# Shift-Rgisters.net
KiCad netlist of a schematic drawn in EAGLE
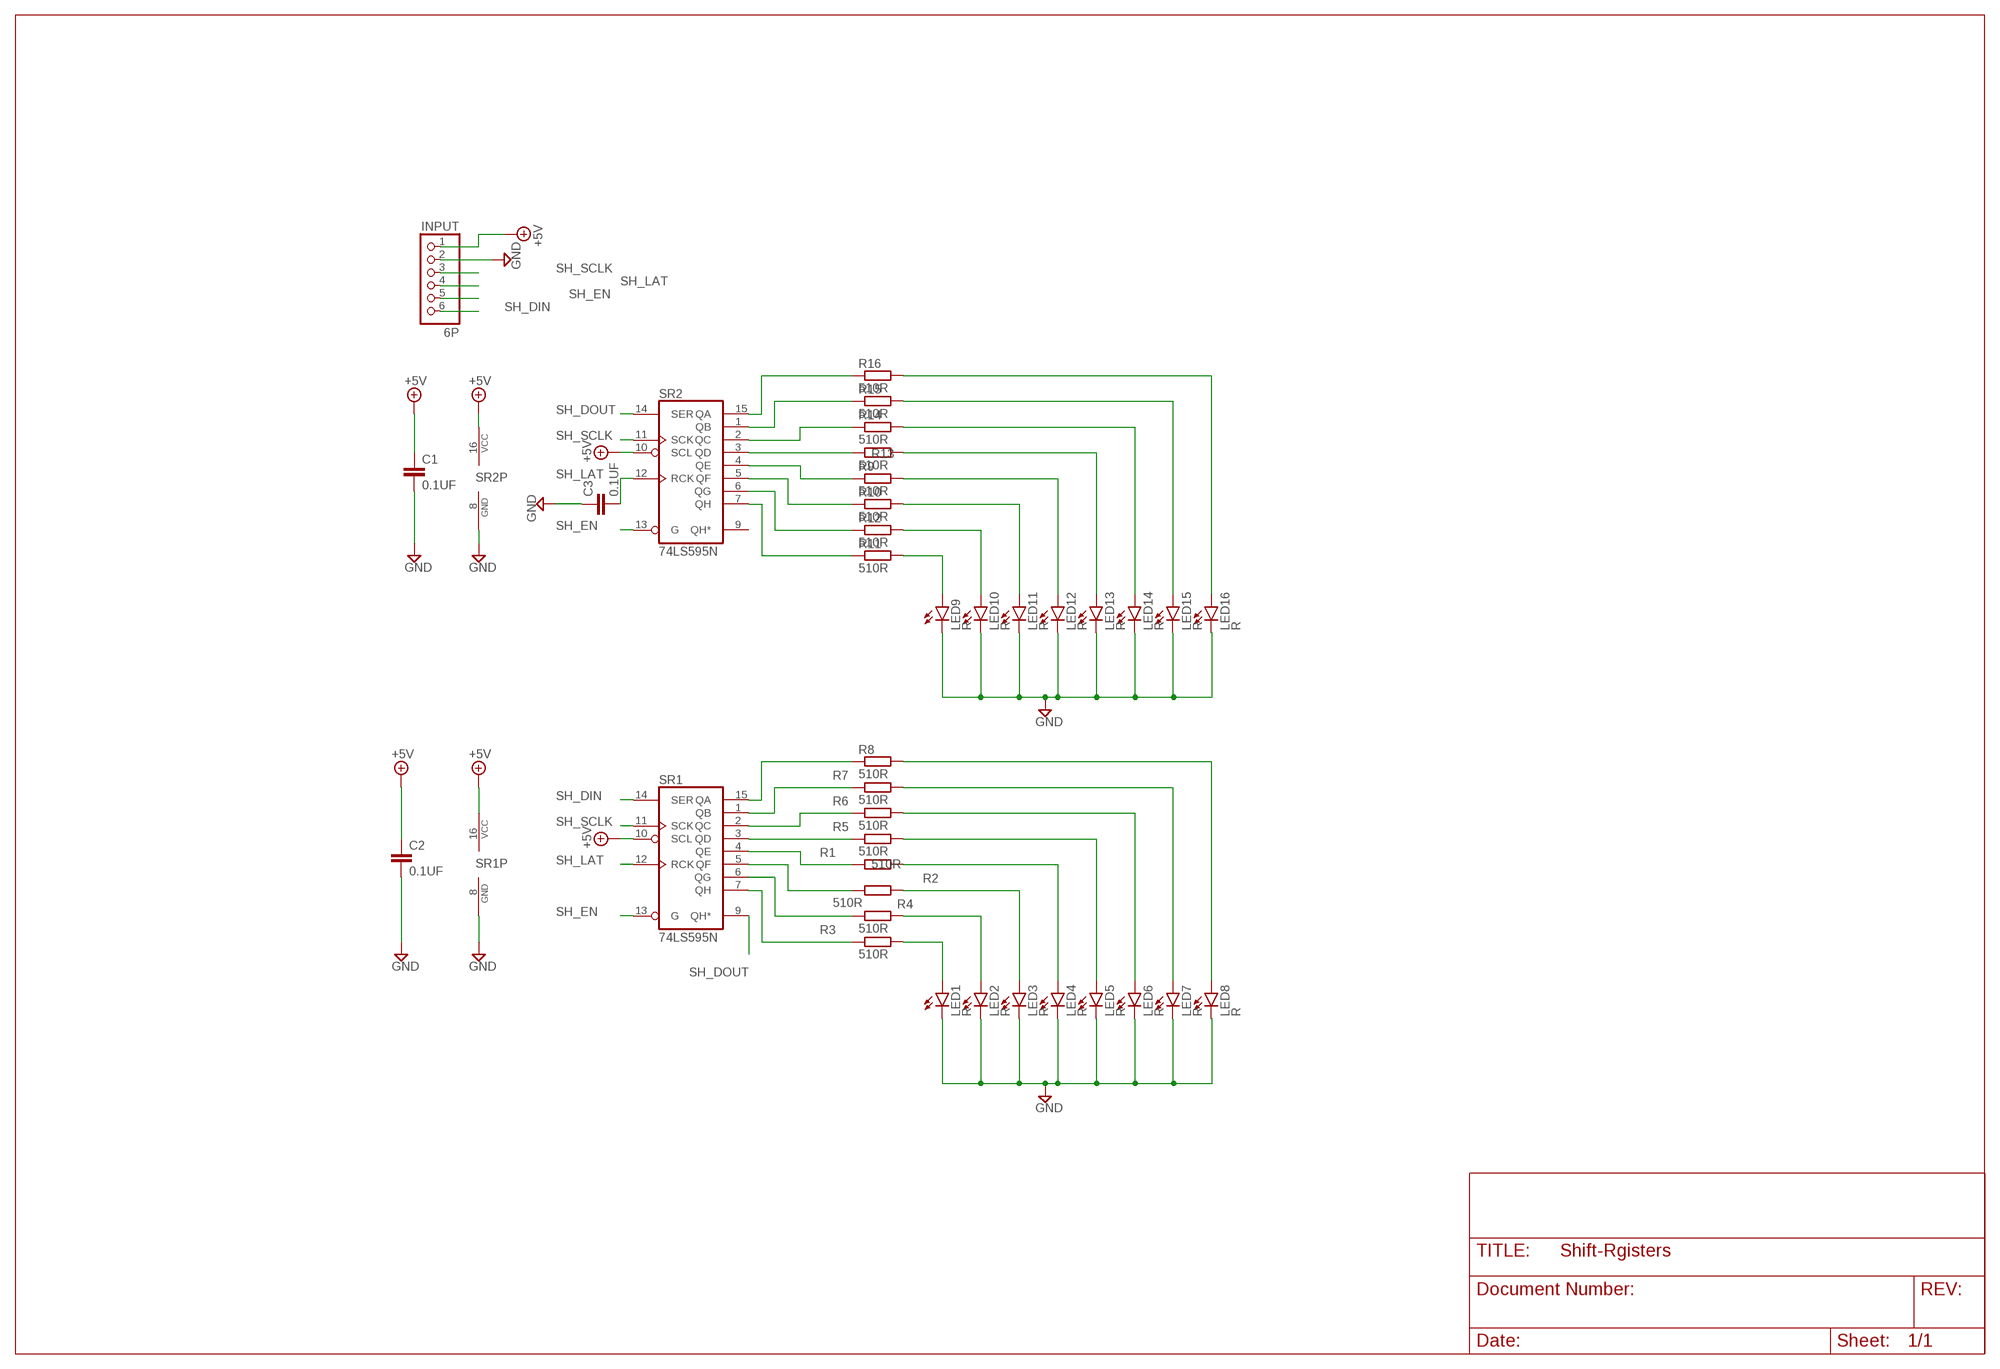
[diagram p0: schematic, sheet 1]

(export (version "E")
  (design (tool "Eeschema 10.0.6"))
  (components
    (comp (ref "C1")
      (value "0.1UF")
      (footprint "eagle-import:C050-030X075")
      (libsource (lib "eagle-import") (part "C-EU050-030X075"))
    )
    (comp (ref "C2")
      (value "0.1UF")
      (footprint "eagle-import:C050-030X075")
      (libsource (lib "eagle-import") (part "C-EU050-030X075"))
    )
    (comp (ref "C3")
      (value "0.1UF")
      (footprint "eagle-import:C050-030X075")
      (libsource (lib "eagle-import") (part "C-EU050-030X075"))
    )
    (comp (ref "INPUT")
      (value "6P")
      (footprint "eagle-import:1X06")
      (libsource (lib "eagle-import") (part "PINHD-1X6"))
    )
    (comp (ref "LED1")
      (value "R")
      (footprint "eagle-import:LED5MM")
      (libsource (lib "eagle-import") (part "LED5MM"))
    )
    (comp (ref "LED2")
      (value "R")
      (footprint "eagle-import:LED5MM")
      (libsource (lib "eagle-import") (part "LED5MM"))
    )
    (comp (ref "LED3")
      (value "R")
      (footprint "eagle-import:LED5MM")
      (libsource (lib "eagle-import") (part "LED5MM"))
    )
    (comp (ref "LED4")
      (value "R")
      (footprint "eagle-import:LED5MM")
      (libsource (lib "eagle-import") (part "LED5MM"))
    )
    (comp (ref "LED5")
      (value "R")
      (footprint "eagle-import:LED5MM")
      (libsource (lib "eagle-import") (part "LED5MM"))
    )
    (comp (ref "LED6")
      (value "R")
      (footprint "eagle-import:LED5MM")
      (libsource (lib "eagle-import") (part "LED5MM"))
    )
    (comp (ref "LED7")
      (value "R")
      (footprint "eagle-import:LED5MM")
      (libsource (lib "eagle-import") (part "LED5MM"))
    )
    (comp (ref "LED8")
      (value "R")
      (footprint "eagle-import:LED5MM")
      (libsource (lib "eagle-import") (part "LED5MM"))
    )
    (comp (ref "LED9")
      (value "R")
      (footprint "eagle-import:LED5MM")
      (libsource (lib "eagle-import") (part "LED5MM"))
    )
    (comp (ref "LED10")
      (value "R")
      (footprint "eagle-import:LED5MM")
      (libsource (lib "eagle-import") (part "LED5MM"))
    )
    (comp (ref "LED11")
      (value "R")
      (footprint "eagle-import:LED5MM")
      (libsource (lib "eagle-import") (part "LED5MM"))
    )
    (comp (ref "LED12")
      (value "R")
      (footprint "eagle-import:LED5MM")
      (libsource (lib "eagle-import") (part "LED5MM"))
    )
    (comp (ref "LED13")
      (value "R")
      (footprint "eagle-import:LED5MM")
      (libsource (lib "eagle-import") (part "LED5MM"))
    )
    (comp (ref "LED14")
      (value "R")
      (footprint "eagle-import:LED5MM")
      (libsource (lib "eagle-import") (part "LED5MM"))
    )
    (comp (ref "LED15")
      (value "R")
      (footprint "eagle-import:LED5MM")
      (libsource (lib "eagle-import") (part "LED5MM"))
    )
    (comp (ref "LED16")
      (value "R")
      (footprint "eagle-import:LED5MM")
      (libsource (lib "eagle-import") (part "LED5MM"))
    )
    (comp (ref "R1")
      (value "510R")
      (footprint "eagle-import:0207_10")
      (libsource (lib "eagle-import") (part "R-EU_0207/10"))
    )
    (comp (ref "R2")
      (value "510R")
      (footprint "eagle-import:0207_10")
      (libsource (lib "eagle-import") (part "R-EU_0207/10"))
    )
    (comp (ref "R3")
      (value "510R")
      (footprint "eagle-import:0207_10")
      (libsource (lib "eagle-import") (part "R-EU_0207/10"))
    )
    (comp (ref "R4")
      (value "510R")
      (footprint "eagle-import:0207_10")
      (libsource (lib "eagle-import") (part "R-EU_0207/10"))
    )
    (comp (ref "R5")
      (value "510R")
      (footprint "eagle-import:0207_10")
      (libsource (lib "eagle-import") (part "R-EU_0207/10"))
    )
    (comp (ref "R6")
      (value "510R")
      (footprint "eagle-import:0207_10")
      (libsource (lib "eagle-import") (part "R-EU_0207/10"))
    )
    (comp (ref "R7")
      (value "510R")
      (footprint "eagle-import:0207_10")
      (libsource (lib "eagle-import") (part "R-EU_0207/10"))
    )
    (comp (ref "R8")
      (value "510R")
      (footprint "eagle-import:0207_10")
      (libsource (lib "eagle-import") (part "R-EU_0207/10"))
    )
    (comp (ref "R9")
      (value "510R")
      (footprint "eagle-import:0207_10")
      (libsource (lib "eagle-import") (part "R-EU_0207/10"))
    )
    (comp (ref "R10")
      (value "510R")
      (footprint "eagle-import:0207_10")
      (libsource (lib "eagle-import") (part "R-EU_0207/10"))
    )
    (comp (ref "R11")
      (value "510R")
      (footprint "eagle-import:0207_10")
      (libsource (lib "eagle-import") (part "R-EU_0207/10"))
    )
    (comp (ref "R12")
      (value "510R")
      (footprint "eagle-import:0207_10")
      (libsource (lib "eagle-import") (part "R-EU_0207/10"))
    )
    (comp (ref "R13")
      (value "510R")
      (footprint "eagle-import:0207_10")
      (libsource (lib "eagle-import") (part "R-EU_0207/10"))
    )
    (comp (ref "R14")
      (value "510R")
      (footprint "eagle-import:0207_10")
      (libsource (lib "eagle-import") (part "R-EU_0207/10"))
    )
    (comp (ref "R15")
      (value "510R")
      (footprint "eagle-import:0207_10")
      (libsource (lib "eagle-import") (part "R-EU_0207/10"))
    )
    (comp (ref "R16")
      (value "510R")
      (footprint "eagle-import:0207_10")
      (libsource (lib "eagle-import") (part "R-EU_0207/10"))
    )
    (comp (ref "SR1")
      (value "74LS595N")
      (footprint "eagle-import:DIL16")
      (libsource (lib "eagle-import") (part "74595NLS"))
    )
    (comp (ref "SR2")
      (value "74LS595N")
      (footprint "eagle-import:DIL16")
      (libsource (lib "eagle-import") (part "74595NLS"))
    )
  )
  (nets
    (net (code "1") (name "+5V") (class "Default")
      (node (ref "C1") (pin "1") (pinfunction "1_1") (pintype "passive"))
      (node (ref "C2") (pin "1") (pinfunction "1_1") (pintype "passive"))
      (node (ref "INPUT") (pin "1") (pinfunction "1_1") (pintype "passive"))
      (node (ref "SR1") (pin "10") (pinfunction "SCL_10") (pintype "input"))
      (node (ref "SR1") (pin "16") (pinfunction "VCC_16") (pintype "power_in"))
      (node (ref "SR2") (pin "10") (pinfunction "SCL_10") (pintype "input"))
      (node (ref "SR2") (pin "16") (pinfunction "VCC_16") (pintype "power_in"))
    )
    (net (code "2") (name "/SH_DIN") (class "Default")
      (node (ref "INPUT") (pin "6") (pinfunction "6_6") (pintype "passive"))
      (node (ref "SR1") (pin "14") (pinfunction "SER_14") (pintype "input"))
    )
    (net (code "3") (name "/SH_DOUT") (class "Default")
      (node (ref "SR1") (pin "9") (pinfunction "QH*_9") (pintype "tri_state"))
      (node (ref "SR2") (pin "14") (pinfunction "SER_14") (pintype "input"))
    )
    (net (code "4") (name "/SH_EN") (class "Default")
      (node (ref "INPUT") (pin "5") (pinfunction "5_5") (pintype "passive"))
      (node (ref "SR1") (pin "13") (pinfunction "G_13") (pintype "input"))
      (node (ref "SR2") (pin "13") (pinfunction "G_13") (pintype "input"))
    )
    (net (code "5") (name "/SH_LAT") (class "Default")
      (node (ref "C3") (pin "2") (pinfunction "2_2") (pintype "passive"))
      (node (ref "INPUT") (pin "4") (pinfunction "4_4") (pintype "passive"))
      (node (ref "SR1") (pin "12") (pinfunction "RCK_12") (pintype "input"))
      (node (ref "SR2") (pin "12") (pinfunction "RCK_12") (pintype "input"))
    )
    (net (code "6") (name "/SH_SCLK") (class "Default")
      (node (ref "INPUT") (pin "3") (pinfunction "3_3") (pintype "passive"))
      (node (ref "SR1") (pin "11") (pinfunction "SCK_11") (pintype "input"))
      (node (ref "SR2") (pin "11") (pinfunction "SCK_11") (pintype "input"))
    )
    (net (code "7") (name "GND") (class "Default")
      (node (ref "C1") (pin "2") (pinfunction "2_2") (pintype "passive"))
      (node (ref "C2") (pin "2") (pinfunction "2_2") (pintype "passive"))
      (node (ref "C3") (pin "1") (pinfunction "1_1") (pintype "passive"))
      (node (ref "INPUT") (pin "2") (pinfunction "2_2") (pintype "passive"))
      (node (ref "LED1") (pin "K") (pinfunction "C_K") (pintype "passive"))
      (node (ref "LED10") (pin "K") (pinfunction "C_K") (pintype "passive"))
      (node (ref "LED11") (pin "K") (pinfunction "C_K") (pintype "passive"))
      (node (ref "LED12") (pin "K") (pinfunction "C_K") (pintype "passive"))
      (node (ref "LED13") (pin "K") (pinfunction "C_K") (pintype "passive"))
      (node (ref "LED14") (pin "K") (pinfunction "C_K") (pintype "passive"))
      (node (ref "LED15") (pin "K") (pinfunction "C_K") (pintype "passive"))
      (node (ref "LED16") (pin "K") (pinfunction "C_K") (pintype "passive"))
      (node (ref "LED2") (pin "K") (pinfunction "C_K") (pintype "passive"))
      (node (ref "LED3") (pin "K") (pinfunction "C_K") (pintype "passive"))
      (node (ref "LED4") (pin "K") (pinfunction "C_K") (pintype "passive"))
      (node (ref "LED5") (pin "K") (pinfunction "C_K") (pintype "passive"))
      (node (ref "LED6") (pin "K") (pinfunction "C_K") (pintype "passive"))
      (node (ref "LED7") (pin "K") (pinfunction "C_K") (pintype "passive"))
      (node (ref "LED8") (pin "K") (pinfunction "C_K") (pintype "passive"))
      (node (ref "LED9") (pin "K") (pinfunction "C_K") (pintype "passive"))
      (node (ref "SR1") (pin "8") (pinfunction "GND_8") (pintype "power_in"))
      (node (ref "SR2") (pin "8") (pinfunction "GND_8") (pintype "power_in"))
    )
    (net (code "8") (name "Net-(LED1-PadA)") (class "Default")
      (node (ref "LED1") (pin "A") (pinfunction "A_A") (pintype "passive"))
      (node (ref "R3") (pin "2") (pinfunction "2_2") (pintype "passive"))
    )
    (net (code "9") (name "Net-(LED2-PadA)") (class "Default")
      (node (ref "LED2") (pin "A") (pinfunction "A_A") (pintype "passive"))
      (node (ref "R4") (pin "2") (pinfunction "2_2") (pintype "passive"))
    )
    (net (code "10") (name "Net-(LED3-PadA)") (class "Default")
      (node (ref "LED3") (pin "A") (pinfunction "A_A") (pintype "passive"))
      (node (ref "R2") (pin "2") (pinfunction "2_2") (pintype "passive"))
    )
    (net (code "11") (name "Net-(LED4-PadA)") (class "Default")
      (node (ref "LED4") (pin "A") (pinfunction "A_A") (pintype "passive"))
      (node (ref "R1") (pin "2") (pinfunction "2_2") (pintype "passive"))
    )
    (net (code "12") (name "Net-(LED5-PadA)") (class "Default")
      (node (ref "LED5") (pin "A") (pinfunction "A_A") (pintype "passive"))
      (node (ref "R5") (pin "2") (pinfunction "2_2") (pintype "passive"))
    )
    (net (code "13") (name "Net-(LED6-PadA)") (class "Default")
      (node (ref "LED6") (pin "A") (pinfunction "A_A") (pintype "passive"))
      (node (ref "R6") (pin "2") (pinfunction "2_2") (pintype "passive"))
    )
    (net (code "14") (name "Net-(LED7-PadA)") (class "Default")
      (node (ref "LED7") (pin "A") (pinfunction "A_A") (pintype "passive"))
      (node (ref "R7") (pin "2") (pinfunction "2_2") (pintype "passive"))
    )
    (net (code "15") (name "Net-(LED8-PadA)") (class "Default")
      (node (ref "LED8") (pin "A") (pinfunction "A_A") (pintype "passive"))
      (node (ref "R8") (pin "2") (pinfunction "2_2") (pintype "passive"))
    )
    (net (code "16") (name "Net-(LED9-PadA)") (class "Default")
      (node (ref "LED9") (pin "A") (pinfunction "A_A") (pintype "passive"))
      (node (ref "R11") (pin "2") (pinfunction "2_2") (pintype "passive"))
    )
    (net (code "17") (name "Net-(LED10-PadA)") (class "Default")
      (node (ref "LED10") (pin "A") (pinfunction "A_A") (pintype "passive"))
      (node (ref "R12") (pin "2") (pinfunction "2_2") (pintype "passive"))
    )
    (net (code "18") (name "Net-(LED11-PadA)") (class "Default")
      (node (ref "LED11") (pin "A") (pinfunction "A_A") (pintype "passive"))
      (node (ref "R10") (pin "2") (pinfunction "2_2") (pintype "passive"))
    )
    (net (code "19") (name "Net-(LED12-PadA)") (class "Default")
      (node (ref "LED12") (pin "A") (pinfunction "A_A") (pintype "passive"))
      (node (ref "R9") (pin "2") (pinfunction "2_2") (pintype "passive"))
    )
    (net (code "20") (name "Net-(LED13-PadA)") (class "Default")
      (node (ref "LED13") (pin "A") (pinfunction "A_A") (pintype "passive"))
      (node (ref "R13") (pin "2") (pinfunction "2_2") (pintype "passive"))
    )
    (net (code "21") (name "Net-(LED14-PadA)") (class "Default")
      (node (ref "LED14") (pin "A") (pinfunction "A_A") (pintype "passive"))
      (node (ref "R14") (pin "2") (pinfunction "2_2") (pintype "passive"))
    )
    (net (code "22") (name "Net-(LED15-PadA)") (class "Default")
      (node (ref "LED15") (pin "A") (pinfunction "A_A") (pintype "passive"))
      (node (ref "R15") (pin "2") (pinfunction "2_2") (pintype "passive"))
    )
    (net (code "23") (name "Net-(LED16-PadA)") (class "Default")
      (node (ref "LED16") (pin "A") (pinfunction "A_A") (pintype "passive"))
      (node (ref "R16") (pin "2") (pinfunction "2_2") (pintype "passive"))
    )
    (net (code "24") (name "Net-(SR1A-QA)") (class "Default")
      (node (ref "R8") (pin "1") (pinfunction "1_1") (pintype "passive"))
      (node (ref "SR1") (pin "15") (pinfunction "QA_15") (pintype "tri_state"))
    )
    (net (code "25") (name "Net-(SR1A-QB)") (class "Default")
      (node (ref "R7") (pin "1") (pinfunction "1_1") (pintype "passive"))
      (node (ref "SR1") (pin "1") (pinfunction "QB_1") (pintype "tri_state"))
    )
    (net (code "26") (name "Net-(SR1A-QC)") (class "Default")
      (node (ref "R6") (pin "1") (pinfunction "1_1") (pintype "passive"))
      (node (ref "SR1") (pin "2") (pinfunction "QC_2") (pintype "tri_state"))
    )
    (net (code "27") (name "Net-(SR1A-QD)") (class "Default")
      (node (ref "R5") (pin "1") (pinfunction "1_1") (pintype "passive"))
      (node (ref "SR1") (pin "3") (pinfunction "QD_3") (pintype "tri_state"))
    )
    (net (code "28") (name "Net-(SR1A-QE)") (class "Default")
      (node (ref "R1") (pin "1") (pinfunction "1_1") (pintype "passive"))
      (node (ref "SR1") (pin "4") (pinfunction "QE_4") (pintype "tri_state"))
    )
    (net (code "29") (name "Net-(SR1A-QF)") (class "Default")
      (node (ref "R2") (pin "1") (pinfunction "1_1") (pintype "passive"))
      (node (ref "SR1") (pin "5") (pinfunction "QF_5") (pintype "tri_state"))
    )
    (net (code "30") (name "Net-(SR1A-QG)") (class "Default")
      (node (ref "R4") (pin "1") (pinfunction "1_1") (pintype "passive"))
      (node (ref "SR1") (pin "6") (pinfunction "QG_6") (pintype "tri_state"))
    )
    (net (code "31") (name "Net-(SR1A-QH)") (class "Default")
      (node (ref "R3") (pin "1") (pinfunction "1_1") (pintype "passive"))
      (node (ref "SR1") (pin "7") (pinfunction "QH_7") (pintype "tri_state"))
    )
    (net (code "32") (name "Net-(SR2A-QA)") (class "Default")
      (node (ref "R16") (pin "1") (pinfunction "1_1") (pintype "passive"))
      (node (ref "SR2") (pin "15") (pinfunction "QA_15") (pintype "tri_state"))
    )
    (net (code "33") (name "Net-(SR2A-QB)") (class "Default")
      (node (ref "R15") (pin "1") (pinfunction "1_1") (pintype "passive"))
      (node (ref "SR2") (pin "1") (pinfunction "QB_1") (pintype "tri_state"))
    )
    (net (code "34") (name "Net-(SR2A-QC)") (class "Default")
      (node (ref "R14") (pin "1") (pinfunction "1_1") (pintype "passive"))
      (node (ref "SR2") (pin "2") (pinfunction "QC_2") (pintype "tri_state"))
    )
    (net (code "35") (name "Net-(SR2A-QD)") (class "Default")
      (node (ref "R13") (pin "1") (pinfunction "1_1") (pintype "passive"))
      (node (ref "SR2") (pin "3") (pinfunction "QD_3") (pintype "tri_state"))
    )
    (net (code "36") (name "Net-(SR2A-QE)") (class "Default")
      (node (ref "R9") (pin "1") (pinfunction "1_1") (pintype "passive"))
      (node (ref "SR2") (pin "4") (pinfunction "QE_4") (pintype "tri_state"))
    )
    (net (code "37") (name "Net-(SR2A-QF)") (class "Default")
      (node (ref "R10") (pin "1") (pinfunction "1_1") (pintype "passive"))
      (node (ref "SR2") (pin "5") (pinfunction "QF_5") (pintype "tri_state"))
    )
    (net (code "38") (name "Net-(SR2A-QG)") (class "Default")
      (node (ref "R12") (pin "1") (pinfunction "1_1") (pintype "passive"))
      (node (ref "SR2") (pin "6") (pinfunction "QG_6") (pintype "tri_state"))
    )
    (net (code "39") (name "Net-(SR2A-QH)") (class "Default")
      (node (ref "R11") (pin "1") (pinfunction "1_1") (pintype "passive"))
      (node (ref "SR2") (pin "7") (pinfunction "QH_7") (pintype "tri_state"))
    )
    (net (code "40") (name "unconnected-(SR2A-QH*-Pad9)") (class "Default")
      (node (ref "SR2") (pin "9") (pinfunction "QH*_9") (pintype "tri_state"))
    )
  )
)
